# HLib-ADCDevices.net
KiCad netlist of a schematic drawn in Altium Designer
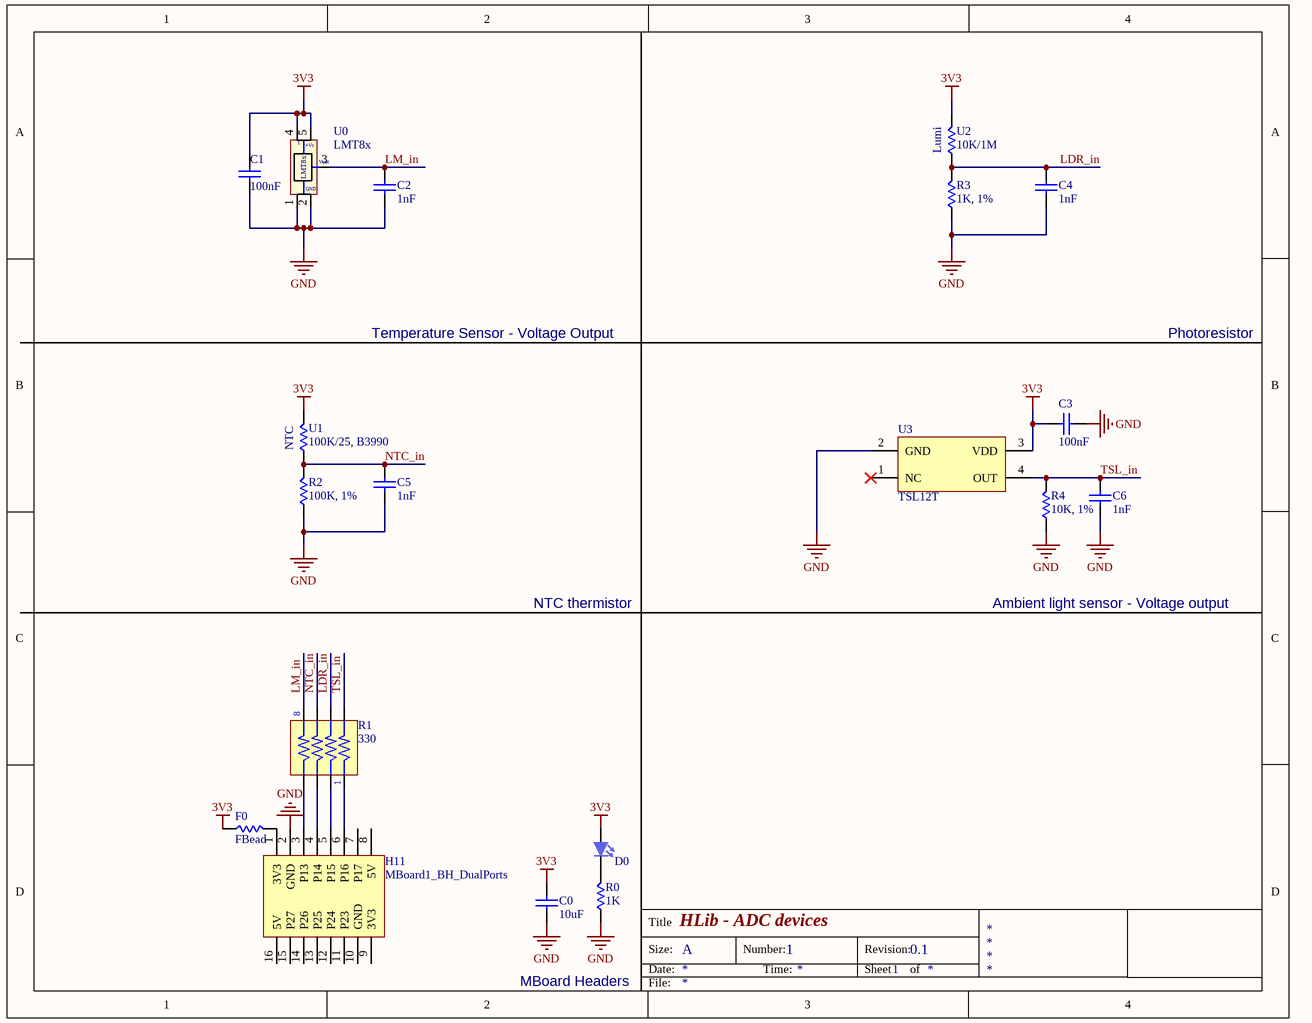
[diagram p0: HLib-ADCDevices.SchDoc]

(export (version "E")
  (design (tool "Eeschema 10.0.6"))
  (components
    (comp (ref "C0")
      (value "10uF")
      (footprint "SM_0805_C_CERAMIC")
      (description "Non-polarity ceramic capacitor")
      (fields (field (name "Comment") "C_Ceramic") (field (name "PUBLISHER") "Altium Limited"))
      (libsource (lib "HLib_discrete_sch") (part "C_Ceramic"))
    )
    (comp (ref "C1")
      (value "100nF")
      (footprint "SM_0805_C_CERAMIC")
      (description "Non-polarity ceramic capacitor")
      (fields (field (name "Comment") "C_Ceramic") (field (name "PUBLISHER") "Altium Limited"))
      (libsource (lib "HLib_discrete_sch") (part "C_Ceramic"))
    )
    (comp (ref "C2")
      (value "1nF")
      (footprint "SM_0805_C_CERAMIC")
      (description "Non-polarity ceramic capacitor")
      (fields (field (name "Comment") "C_Ceramic") (field (name "PUBLISHER") "Altium Limited"))
      (libsource (lib "HLib_discrete_sch") (part "C_Ceramic"))
    )
    (comp (ref "C3")
      (value "100nF")
      (footprint "SM_0805_C_CERAMIC")
      (description "Non-polarity ceramic capacitor")
      (fields (field (name "Comment") "C_Ceramic") (field (name "PUBLISHER") "Altium Limited"))
      (libsource (lib "HLib_discrete_sch") (part "C_Ceramic"))
    )
    (comp (ref "C4")
      (value "1nF")
      (footprint "SM_0805_C_CERAMIC")
      (description "Non-polarity ceramic capacitor")
      (fields (field (name "Comment") "C_Ceramic") (field (name "PUBLISHER") "Altium Limited"))
      (libsource (lib "HLib_discrete_sch") (part "C_Ceramic"))
    )
    (comp (ref "C5")
      (value "1nF")
      (footprint "SM_0805_C_CERAMIC")
      (description "Non-polarity ceramic capacitor")
      (fields (field (name "Comment") "C_Ceramic") (field (name "PUBLISHER") "Altium Limited"))
      (libsource (lib "HLib_discrete_sch") (part "C_Ceramic"))
    )
    (comp (ref "C6")
      (value "1nF")
      (footprint "SM_0805_C_CERAMIC")
      (description "Non-polarity ceramic capacitor")
      (fields (field (name "Comment") "C_Ceramic") (field (name "PUBLISHER") "Altium Limited"))
      (libsource (lib "HLib_discrete_sch") (part "C_Ceramic"))
    )
    (comp (ref "D0")
      (value "LED")
      (footprint "SM_0805_LED")
      (fields (field (name "PUBLISHER") "Altium Limited"))
      (libsource (lib "HLib_discrete_sch") (part "LED"))
    )
    (comp (ref "F0")
      (value "FBead")
      (footprint "SM_0805_R")
      (description "Resistor")
      (fields (field (name "Comment") "R") (field (name "PUBLISHER") "Altium Limited"))
      (libsource (lib "HLib_discrete_sch") (part "R"))
    )
    (comp (ref "H11")
      (value "MBoard1_BH_DualPorts")
      (footprint "MBoard1_BH_DualPorts")
      (libsource (lib "Nhat_Lib") (part "MBoard1_BH_DualPorts"))
    )
    (comp (ref "R0")
      (value "1K")
      (footprint "SM_0805_R")
      (description "Resistor")
      (fields (field (name "Comment") "R") (field (name "PUBLISHER") "Altium Limited"))
      (libsource (lib "HLib_discrete_sch") (part "R"))
    )
    (comp (ref "R1") (value "330") (footprint "RA4") (libsource (lib "Nhat_Lib") (part "RA4")))
    (comp (ref "R2")
      (value "100K, 1%")
      (footprint "SM_0805_R")
      (description "Resistor")
      (fields (field (name "PUBLISHER") "Altium Limited"))
      (libsource (lib "HLib_discrete_sch") (part "R"))
    )
    (comp (ref "R3")
      (value "1K, 1%")
      (footprint "SM_0805_R")
      (description "Resistor")
      (fields (field (name "PUBLISHER") "Altium Limited"))
      (libsource (lib "HLib_discrete_sch") (part "R"))
    )
    (comp (ref "R4")
      (value "10K, 1%")
      (footprint "SM_0805_R")
      (description "Resistor")
      (fields (field (name "PUBLISHER") "Altium Limited"))
      (libsource (lib "HLib_discrete_sch") (part "R"))
    )
    (comp (ref "U0") (value "LMT8x") (footprint "SC70-5") (libsource (lib "Nhat_Lib") (part "LMT8x")))
    (comp (ref "U1")
      (value "NTC")
      (footprint "R1/4W")
      (description "Resistor")
      (fields (field (name "ALTIUM_VALUE") "100K/25, B3990") (field (name "PUBLISHER") "Altium Limited"))
      (libsource (lib "HLib_discrete_sch") (part "R"))
    )
    (comp (ref "U2")
      (value "Lumi")
      (footprint "PhotoRes-5mm")
      (description "Resistor")
      (fields (field (name "ALTIUM_VALUE") "10K/1M") (field (name "PUBLISHER") "Altium Limited"))
      (libsource (lib "HLib_discrete_sch") (part "R"))
    )
    (comp (ref "U3")
      (value "TSL12T")
      (footprint "4-LEAD SMD")
      (description "AMS TSL12T Ambient light sensor, Voltage output")
      (libsource (lib "Nhat_Lib") (part "TSL12T"))
    )
  )
  (nets
    (net (code "1") (name "/LDR_in") (class "Default")
      (node (ref "C4") (pin "2") (pinfunction "2_2") (pintype "passive"))
      (node (ref "R1") (pin "4") (pinfunction "4_4") (pintype "passive"))
      (node (ref "R3") (pin "2") (pinfunction "2_2") (pintype "passive"))
      (node (ref "U2") (pin "1") (pinfunction "1_1") (pintype "passive"))
    )
    (net (code "2") (name "/LM_in") (class "Default")
      (node (ref "C2") (pin "2") (pinfunction "2_2") (pintype "passive"))
      (node (ref "R1") (pin "8") (pinfunction "8_8") (pintype "passive"))
      (node (ref "U0") (pin "3") (pinfunction "Vout_3") (pintype "passive"))
    )
    (net (code "3") (name "/NTC_in") (class "Default")
      (node (ref "C5") (pin "2") (pinfunction "2_2") (pintype "passive"))
      (node (ref "R1") (pin "6") (pinfunction "6_6") (pintype "passive"))
      (node (ref "R2") (pin "2") (pinfunction "2_2") (pintype "passive"))
      (node (ref "U1") (pin "1") (pinfunction "1_1") (pintype "passive"))
    )
    (net (code "4") (name "/TSL_in") (class "Default")
      (node (ref "C6") (pin "2") (pinfunction "2_2") (pintype "passive"))
      (node (ref "R1") (pin "2") (pinfunction "2_2") (pintype "passive"))
      (node (ref "R4") (pin "2") (pinfunction "2_2") (pintype "passive"))
      (node (ref "U3") (pin "4") (pinfunction "OUT_4") (pintype "passive"))
    )
    (net (code "5") (name "3V3") (class "Default")
      (node (ref "C0") (pin "2") (pinfunction "2_2") (pintype "passive"))
      (node (ref "C1") (pin "2") (pinfunction "2_2") (pintype "passive"))
      (node (ref "C3") (pin "2") (pinfunction "2_2") (pintype "passive"))
      (node (ref "D0") (pin "1") (pinfunction "A_1") (pintype "passive"))
      (node (ref "F0") (pin "1") (pinfunction "1_1") (pintype "passive"))
      (node (ref "U0") (pin "4") (pinfunction "+Vs_4") (pintype "passive"))
      (node (ref "U0") (pin "5") (pinfunction "+Vs_5") (pintype "passive"))
      (node (ref "U1") (pin "2") (pinfunction "2_2") (pintype "passive"))
      (node (ref "U2") (pin "2") (pinfunction "2_2") (pintype "passive"))
      (node (ref "U3") (pin "3") (pinfunction "VDD_3") (pintype "passive"))
    )
    (net (code "6") (name "GND") (class "Default")
      (node (ref "C0") (pin "1") (pinfunction "1_1") (pintype "passive"))
      (node (ref "C1") (pin "1") (pinfunction "1_1") (pintype "passive"))
      (node (ref "C2") (pin "1") (pinfunction "1_1") (pintype "passive"))
      (node (ref "C3") (pin "1") (pinfunction "1_1") (pintype "passive"))
      (node (ref "C4") (pin "1") (pinfunction "1_1") (pintype "passive"))
      (node (ref "C5") (pin "1") (pinfunction "1_1") (pintype "passive"))
      (node (ref "C6") (pin "1") (pinfunction "1_1") (pintype "passive"))
      (node (ref "H11") (pin "2") (pinfunction "GND_2") (pintype "passive"))
      (node (ref "R0") (pin "1") (pinfunction "1_1") (pintype "passive"))
      (node (ref "R2") (pin "1") (pinfunction "1_1") (pintype "passive"))
      (node (ref "R3") (pin "1") (pinfunction "1_1") (pintype "passive"))
      (node (ref "R4") (pin "1") (pinfunction "1_1") (pintype "passive"))
      (node (ref "U0") (pin "1") (pinfunction "-_1") (pintype "passive"))
      (node (ref "U0") (pin "2") (pinfunction "-_2") (pintype "passive"))
      (node (ref "U3") (pin "2") (pinfunction "GND_2") (pintype "passive"))
    )
    (net (code "7") (name "Net-(D0-K)") (class "Default")
      (node (ref "D0") (pin "2") (pinfunction "K_2") (pintype "passive"))
      (node (ref "R0") (pin "2") (pinfunction "2_2") (pintype "passive"))
    )
    (net (code "8") (name "Net-(F0-Pad2)") (class "Default")
      (node (ref "F0") (pin "2") (pinfunction "2_2") (pintype "passive"))
      (node (ref "H11") (pin "1") (pinfunction "3V3_1") (pintype "passive"))
    )
    (net (code "9") (name "Net-(H11-P13)") (class "Default")
      (node (ref "H11") (pin "3") (pinfunction "P13_3") (pintype "passive"))
      (node (ref "R1") (pin "7") (pinfunction "7_7") (pintype "passive"))
    )
    (net (code "10") (name "Net-(H11-P14)") (class "Default")
      (node (ref "H11") (pin "4") (pinfunction "P14_4") (pintype "passive"))
      (node (ref "R1") (pin "5") (pinfunction "5_5") (pintype "passive"))
    )
    (net (code "11") (name "Net-(H11-P15)") (class "Default")
      (node (ref "H11") (pin "5") (pinfunction "P15_5") (pintype "passive"))
      (node (ref "R1") (pin "3") (pinfunction "3_3") (pintype "passive"))
    )
    (net (code "12") (name "Net-(H11-P16)") (class "Default")
      (node (ref "H11") (pin "6") (pinfunction "P16_6") (pintype "passive"))
      (node (ref "R1") (pin "1") (pinfunction "1_1") (pintype "passive"))
    )
    (net (code "13") (name "unconnected-(H11-3V3-Pad9)") (class "Default")
      (node (ref "H11") (pin "9") (pinfunction "3V3_9") (pintype "passive"))
    )
    (net (code "14") (name "unconnected-(H11-5V-Pad8)") (class "Default")
      (node (ref "H11") (pin "8") (pinfunction "5V_8") (pintype "passive"))
    )
    (net (code "15") (name "unconnected-(H11-5V-Pad16)") (class "Default")
      (node (ref "H11") (pin "16") (pinfunction "5V_16") (pintype "passive"))
    )
    (net (code "16") (name "unconnected-(H11-GND-Pad10)") (class "Default")
      (node (ref "H11") (pin "10") (pinfunction "GND_10") (pintype "passive"))
    )
    (net (code "17") (name "unconnected-(H11-P17-Pad7)") (class "Default")
      (node (ref "H11") (pin "7") (pinfunction "P17_7") (pintype "passive"))
    )
    (net (code "18") (name "unconnected-(H11-P23-Pad11)") (class "Default")
      (node (ref "H11") (pin "11") (pinfunction "P23_11") (pintype "passive"))
    )
    (net (code "19") (name "unconnected-(H11-P24-Pad12)") (class "Default")
      (node (ref "H11") (pin "12") (pinfunction "P24_12") (pintype "passive"))
    )
    (net (code "20") (name "unconnected-(H11-P25-Pad13)") (class "Default")
      (node (ref "H11") (pin "13") (pinfunction "P25_13") (pintype "passive"))
    )
    (net (code "21") (name "unconnected-(H11-P26-Pad14)") (class "Default")
      (node (ref "H11") (pin "14") (pinfunction "P26_14") (pintype "passive"))
    )
    (net (code "22") (name "unconnected-(H11-P27-Pad15)") (class "Default")
      (node (ref "H11") (pin "15") (pinfunction "P27_15") (pintype "passive"))
    )
    (net (code "23") (name "unconnected-(U3-NC-Pad1)") (class "Default")
      (node (ref "U3") (pin "1") (pinfunction "NC_1") (pintype "passive+no_connect"))
    )
  )
)
